# Shematic.net
KiCad netlist of a schematic drawn in Altium Designer
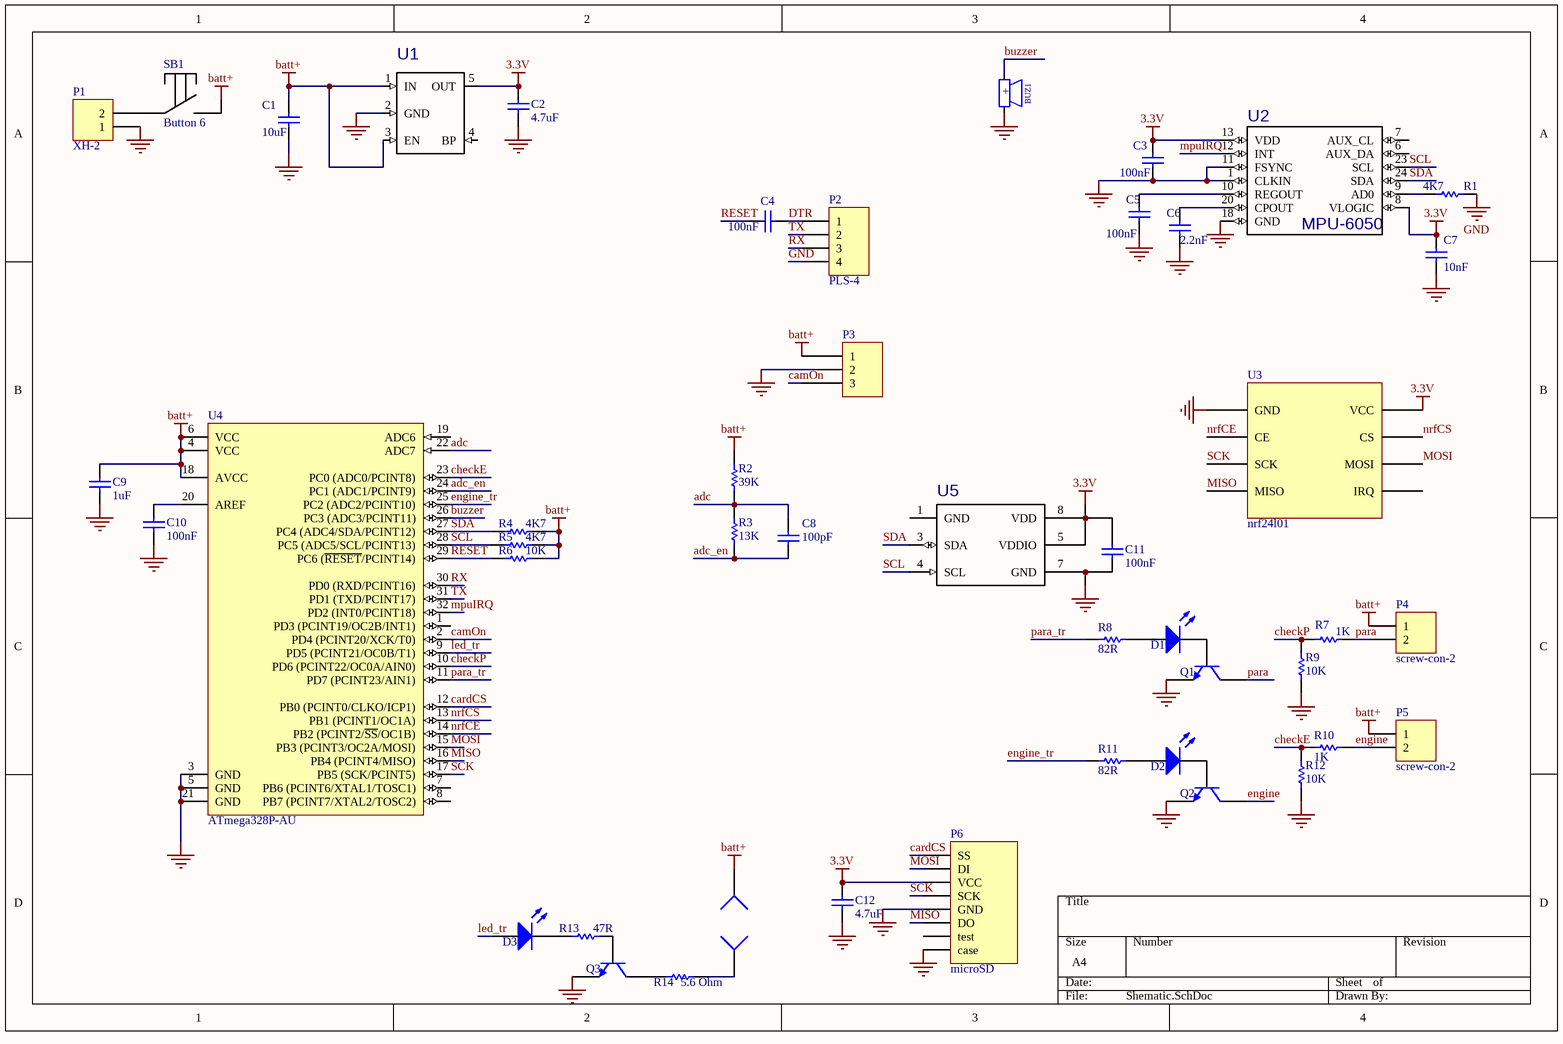
[diagram p0: Shematic.SchDoc]

(export (version "E")
  (design (tool "Eeschema 10.0.6"))
  (components
    (comp (ref "BUZ1")
      (value "Buzzer")
      (footprint "BUZ12X7,6MM")
      (description "BUZ12X7,6MM")
      (libsource (lib "Library") (part "Buzzer"))
    )
    (comp (ref "C1")
      (value "10uF")
      (footprint "CAPC1206(3216)190_N")
      (description "CAP 10uF 50V ±20% 1206 (3216 Metric) Thickness 1.9mm SMD")
      (fields (field (name "TOLERANCE") "Â±20%"))
      (libsource (lib "Altium Content Vault") (part "CMP-1037-04983-1"))
    )
    (comp (ref "C2")
      (value "4.7uF")
      (footprint "CAPC0603(1608)100_N")
      (description "CAP 4.7uF 16V ±20% 0603 (1608 Metric) Thickness 1mm SMD")
      (fields (field (name "TOLERANCE") "Â±20%"))
      (libsource (lib "Altium Content Vault") (part "CMP-1035-02789-1"))
    )
    (comp (ref "C3")
      (value "100nF")
      (footprint "CAPC0603(1608)100_N")
      (description "CAP 100nF 16V ±20% 0603 (1608 Metric) Thickness 1mm SMD")
      (fields (field (name "TOLERANCE") "Â±20%"))
      (libsource (lib "Altium Content Vault") (part "CMP-1035-02585-1"))
    )
    (comp (ref "C4")
      (value "100nF")
      (footprint "CAPC0603(1608)100_N")
      (description "CAP 100nF 16V ±20% 0603 (1608 Metric) Thickness 1mm SMD")
      (fields (field (name "TOLERANCE") "Â±20%"))
      (libsource (lib "Altium Content Vault") (part "CMP-1035-02585-1"))
    )
    (comp (ref "C5")
      (value "100nF")
      (footprint "CAPC0603(1608)100_N")
      (description "CAP 100nF 16V ±20% 0603 (1608 Metric) Thickness 1mm SMD")
      (fields (field (name "TOLERANCE") "Â±20%"))
      (libsource (lib "Altium Content Vault") (part "CMP-1035-02585-1"))
    )
    (comp (ref "C6")
      (value "2.2nF")
      (footprint "CAPC0603(1608)100_L")
      (description "CAP 2.2nF 16V ±20% 0603 (1608 Metric) Thickness 1mm SMD")
      (fields (field (name "TOLERANCE") "Â±20%"))
      (libsource (lib "Altium Content Vault") (part "CMP-1035-02030-1"))
    )
    (comp (ref "C7")
      (value "10nF")
      (footprint "CAPC0603(1608)100_L")
      (description "CAP 10nF 16V ±20% 0603 (1608 Metric) Thickness 1mm SMD")
      (fields (field (name "TOLERANCE") "Â±20%"))
      (libsource (lib "Altium Content Vault") (part "CMP-1035-02312-1"))
    )
    (comp (ref "C8")
      (value "100pF")
      (footprint "CAPC0805(2012)100_L")
      (description "CAP 200pF 16V ±10% 0805 (2012 Metric) Thickness 1mm SMD")
      (fields (field (name "TOLERANCE") "Â±10%"))
      (libsource (lib "Altium Content Vault") (part "CMP-1036-02260-1"))
    )
    (comp (ref "C9")
      (value "1uF")
      (footprint "CAPC0603(1608)100_L")
      (description "CAP 1uF 16V ±20% 0603 (1608 Metric) Thickness 1mm SMD")
      (fields (field (name "TOLERANCE") "Â±20%"))
      (libsource (lib "Altium Content Vault") (part "CMP-1035-02738-1"))
    )
    (comp (ref "C10")
      (value "100nF")
      (footprint "CAPC0603(1608)100_N")
      (description "CAP 100nF 16V ±20% 0603 (1608 Metric) Thickness 1mm SMD")
      (fields (field (name "TOLERANCE") "Â±20%"))
      (libsource (lib "Altium Content Vault") (part "CMP-1035-02585-1"))
    )
    (comp (ref "C11")
      (value "100nF")
      (footprint "CAPC0603(1608)100_N")
      (description "CAP 100nF 16V ±20% 0603 (1608 Metric) Thickness 1mm SMD")
      (fields (field (name "TOLERANCE") "Â±20%"))
      (libsource (lib "Altium Content Vault") (part "CMP-1035-02585-1"))
    )
    (comp (ref "C12")
      (value "4.7uF")
      (footprint "CAPC0603(1608)100_N")
      (description "CAP 4.7uF 16V ±20% 0603 (1608 Metric) Thickness 1mm SMD")
      (fields (field (name "TOLERANCE") "Â±20%"))
      (libsource (lib "Altium Content Vault") (part "CMP-1035-02789-1"))
    )
    (comp (ref "D1")
      (value "~")
      (footprint "LED0805")
      (description "Typical INFRARED GaAs LED")
      (fields (field (name "PUBLISHER") "Altium Limited"))
      (libsource (lib "Library") (part "LED0"))
    )
    (comp (ref "D2")
      (value "~")
      (footprint "LED0805")
      (description "Typical INFRARED GaAs LED")
      (fields (field (name "PUBLISHER") "Altium Limited"))
      (libsource (lib "Library") (part "LED0"))
    )
    (comp (ref "D3")
      (value "~")
      (footprint "LED0805")
      (description "Typical INFRARED GaAs LED")
      (fields (field (name "PUBLISHER") "Altium Limited"))
      (libsource (lib "Library") (part "LED0"))
    )
    (comp (ref "J1")
      (value "~")
      (footprint "PIN1")
      (description "Socket")
      (fields (field (name "PUBLISHER") "Altium Limited"))
      (libsource (lib "Miscellaneous Connectors") (part "Socket"))
    )
    (comp (ref "J2")
      (value "~")
      (footprint "PIN1")
      (description "Socket")
      (fields (field (name "PUBLISHER") "Altium Limited"))
      (libsource (lib "Miscellaneous Connectors") (part "Socket"))
    )
    (comp (ref "P1")
      (value "XH-2")
      (footprint "Library_pcb:XH-2")
      (description "XH 2-pin, 2.4mm pitch")
      (fields (field (name "PUBLISHER") "Altium Limited"))
      (libsource (lib "Library") (part "XH-2"))
    )
    (comp (ref "P2")
      (value "PLS-4")
      (footprint "Connectors:PLS-4")
      (description "Single row pins")
      (libsource (lib "Connectors") (part "PLS-4"))
    )
    (comp (ref "P3")
      (value "XH2.54-3")
      (footprint "Connectors:XH2.54-3")
      (libsource (lib "Connectors") (part "XH2.54-3"))
    )
    (comp (ref "P4")
      (value "screw-con-2")
      (footprint "Library_pcb:screw-con-2")
      (description "screw con 2-pin, 5.08mm pitch")
      (fields (field (name "PUBLISHER") "Altium Limited"))
      (libsource (lib "Library") (part "screw-con-2"))
    )
    (comp (ref "P5")
      (value "screw-con-2")
      (footprint "Library_pcb:screw-con-2")
      (description "screw con 2-pin, 5.08mm pitch")
      (fields (field (name "PUBLISHER") "Altium Limited"))
      (libsource (lib "Library") (part "screw-con-2"))
    )
    (comp (ref "P6")
      (value "microSD")
      (footprint "Library_pcb:microSD holder")
      (description "microSD holder")
      (fields (field (name "PUBLISHER") "Altium Limited"))
      (libsource (lib "Library") (part "microSD"))
    )
    (comp (ref "Q1")
      (value "MMBT2222A")
      (footprint "INF-SOT23_L")
      (description "NPN Silicon Switching Transistor, 40 V VCEO, 600 mA IC, SOT23, Reel, Green")
      (fields (field (name "MANUFACTURER") "Infineon"))
      (libsource (lib "Altium Content Vault") (part "CMP-1178-00009-1"))
    )
    (comp (ref "Q2")
      (value "MMBT2222A")
      (footprint "INF-SOT23_N")
      (description "NPN Silicon Switching Transistor, 40 V VCEO, 600 mA IC, SOT23, Reel, Green")
      (fields (field (name "MANUFACTURER") "Infineon"))
      (libsource (lib "Altium Content Vault") (part "CMP-1178-00009-1"))
    )
    (comp (ref "Q3")
      (value "MMBT2222A")
      (footprint "INF-SOT23_M")
      (description "NPN Silicon Switching Transistor, 40 V VCEO, 600 mA IC, SOT23, Reel, Green")
      (fields (field (name "MANUFACTURER") "Infineon"))
      (libsource (lib "Altium Content Vault") (part "CMP-1178-00009-1"))
    )
    (comp (ref "R1")
      (value "4K7")
      (footprint "RESC0603(1608)_N")
      (description "4K7 0.1W 5% 0603 (1608 Metric)  SMD")
      (fields (field (name "TOLERANCE") "5 %") (field (name "POWER") "0.1 W"))
      (libsource (lib "Altium Content Vault") (part "CMP-1012-00090-1"))
    )
    (comp (ref "R2")
      (value "39K")
      (footprint "Miscellaneous Devices:6-0805_L")
      (description "39K 0.25W 5% 1206 (3216 Metric)  SMD")
      (fields (field (name "TOLERANCE") "5 %") (field (name "POWER") "0.25 W"))
      (libsource (lib "altium-import") (part "root_1_CMP-1014-00112-1_"))
    )
    (comp (ref "R3")
      (value "13K")
      (footprint "RESC0805(2012)_L")
      (description "13K 0.125W 5% 0805 (2012 Metric)  SMD")
      (fields (field (name "POWER") "0.125 W") (field (name "TOLERANCE") "5 %"))
      (libsource (lib "Altium Content Vault") (part "CMP-1013-00101-1"))
    )
    (comp (ref "R4")
      (value "4K7")
      (footprint "RESC0603(1608)_N")
      (description "4K7 0.1W 5% 0603 (1608 Metric)  SMD")
      (fields (field (name "TOLERANCE") "5 %") (field (name "POWER") "0.1 W"))
      (libsource (lib "Altium Content Vault") (part "CMP-1012-00090-1"))
    )
    (comp (ref "R5")
      (value "4K7")
      (footprint "RESC0603(1608)_N")
      (description "4K7 0.1W 5% 0603 (1608 Metric)  SMD")
      (fields (field (name "TOLERANCE") "5 %") (field (name "POWER") "0.1 W"))
      (libsource (lib "Altium Content Vault") (part "CMP-1012-00090-1"))
    )
    (comp (ref "R6")
      (value "10K")
      (footprint "Miscellaneous Devices:6-0805_L")
      (fields (field (name "POWER") "0.25 W") (field (name "TOLERANCE") "5 %"))
      (libsource (lib "altium-import") (part "root_0_CMP-1014-00098-1_"))
    )
    (comp (ref "R7")
      (value "1K")
      (footprint "RESC0805(2012)_N")
      (description "1K 0.125W 5% 0805 (2012 Metric)  SMD")
      (fields (field (name "POWER") "0.125 W") (field (name "TOLERANCE") "5 %"))
      (libsource (lib "Altium Content Vault") (part "CMP-1013-00074-1"))
    )
    (comp (ref "R8")
      (value "82R")
      (footprint "RESC0805(2012)_L")
      (description "2R4 0.125W 5% 0805 (2012 Metric)  SMD")
      (fields (field (name "POWER") "0.125 W") (field (name "TOLERANCE") "5 %"))
      (libsource (lib "Altium Content Vault") (part "CMP-1013-00011-1"))
    )
    (comp (ref "R9")
      (value "10K")
      (footprint "RESC0805(2012)_L")
      (description "10K 0.125W 5% 0805 (2012 Metric)  SMD")
      (fields (field (name "POWER") "0.125 W") (field (name "TOLERANCE") "5 %"))
      (libsource (lib "Altium Content Vault") (part "CMP-1013-00098-1"))
    )
    (comp (ref "R10")
      (value "1K")
      (footprint "RESC1206(3216)_N")
      (description "1K 0.25W 5% 1206 (3216 Metric)  SMD")
      (fields (field (name "TOLERANCE") "5 %") (field (name "POWER") "0.25 W"))
      (libsource (lib "Altium Content Vault") (part "CMP-1014-00074-1"))
    )
    (comp (ref "R11")
      (value "82R")
      (footprint "RESC0805(2012)_L")
      (description "2R4 0.125W 5% 0805 (2012 Metric)  SMD")
      (fields (field (name "POWER") "0.125 W") (field (name "TOLERANCE") "5 %"))
      (libsource (lib "Altium Content Vault") (part "CMP-1013-00011-1"))
    )
    (comp (ref "R12")
      (value "10K")
      (footprint "RESC0805(2012)_L")
      (description "10K 0.125W 5% 0805 (2012 Metric)  SMD")
      (fields (field (name "POWER") "0.125 W") (field (name "TOLERANCE") "5 %"))
      (libsource (lib "Altium Content Vault") (part "CMP-1013-00098-1"))
    )
    (comp (ref "R13")
      (value "47R")
      (footprint "RESC0805(2012)_N")
      (description "270R 0.125W 5% 0805 (2012 Metric)  SMD")
      (fields (field (name "POWER") "0.125 W") (field (name "TOLERANCE") "5 %"))
      (libsource (lib "Altium Content Vault") (part "CMP-1013-00060-1"))
    )
    (comp (ref "R14")
      (value "5.6 Ohm")
      (footprint "RESC0805(2012)_M")
      (description "100R 0.125W 5% 0805 (2012 Metric)  SMD")
      (fields (field (name "TOLERANCE") "5 %") (field (name "POWER") "0.125 W"))
      (libsource (lib "Altium Content Vault") (part "CMP-1013-00050-1"))
    )
    (comp (ref "SB1")
      (value "Button 6")
      (footprint "Library_pcb:Button - 6 mm")
      (libsource (lib "Library") (part "Button 6"))
    )
    (comp (ref "U1")
      (value "MIC5205")
      (footprint "SOT23-5L_M")
      (description "LDO (KB33)")
      (libsource (lib "Library") (part "MIC5205"))
    )
    (comp (ref "U2")
      (value "MPU-6050")
      (footprint "QFN-24-4MM2")
      (libsource (lib "Library") (part "MPU-6050"))
    )
    (comp (ref "U3")
      (value "nrf24l01")
      (footprint "NRF24l01 ant")
      (description "Wirless module 2.4GHz")
      (libsource (lib "Library") (part "NRF24L01"))
    )
    (comp (ref "U4")
      (value "ATmega328P-AU")
      (footprint "32A_M")
      (libsource (lib "Altium Content Vault") (part "MC-8B-ATM48-SQ32"))
    )
    (comp (ref "U5")
      (value "BMP280")
      (footprint "Library_pcb:BMP280")
      (libsource (lib "Library") (part "BMP280"))
    )
  )
  (nets
    (net (code "1") (name "/DTR") (class "Default")
      (node (ref "C4") (pin "2") (pinfunction "2_2") (pintype "passive"))
      (node (ref "P2") (pin "1") (pinfunction "1_1") (pintype "passive"))
    )
    (net (code "2") (name "/MISO") (class "Default")
      (node (ref "P6") (pin "7") (pinfunction "DO_7") (pintype "passive"))
      (node (ref "U3") (pin "7") (pinfunction "MISO_7") (pintype "passive"))
      (node (ref "U4") (pin "16") (pinfunction "PB4_(PCINT4/MISO)_16") (pintype "bidirectional"))
    )
    (net (code "3") (name "/MOSI") (class "Default")
      (node (ref "P6") (pin "3") (pinfunction "DI_3") (pintype "passive"))
      (node (ref "U3") (pin "6") (pinfunction "MOSI_6") (pintype "passive"))
      (node (ref "U4") (pin "15") (pinfunction "PB3_(PCINT3/OC2A/MOSI)_15") (pintype "bidirectional"))
    )
    (net (code "4") (name "/RESET") (class "Default")
      (node (ref "C4") (pin "1") (pinfunction "1_1") (pintype "passive"))
      (node (ref "R6") (pin "1") (pinfunction "1_1") (pintype "passive"))
      (node (ref "U4") (pin "29") (pinfunction "PC6_(~{RESET}/PCINT14)_29") (pintype "bidirectional"))
    )
    (net (code "5") (name "/RX") (class "Default")
      (node (ref "P2") (pin "3") (pinfunction "3_3") (pintype "passive"))
      (node (ref "U4") (pin "30") (pinfunction "PD0_(RXD/PCINT16)_30") (pintype "bidirectional"))
    )
    (net (code "6") (name "/SCK") (class "Default")
      (node (ref "P6") (pin "5") (pinfunction "SCK_5") (pintype "passive"))
      (node (ref "U3") (pin "5") (pinfunction "SCK_5") (pintype "passive"))
      (node (ref "U4") (pin "17") (pinfunction "PB5_(SCK/PCINT5)_17") (pintype "bidirectional"))
    )
    (net (code "7") (name "/SCL") (class "Default")
      (node (ref "R5") (pin "1") (pinfunction "1_1") (pintype "passive"))
      (node (ref "U2") (pin "23") (pinfunction "SCL_23") (pintype "bidirectional"))
      (node (ref "U4") (pin "28") (pinfunction "PC5_(ADC5/SCL/PCINT13)_28") (pintype "bidirectional"))
      (node (ref "U5") (pin "4") (pinfunction "SCL_4") (pintype "input"))
    )
    (net (code "8") (name "/SDA") (class "Default")
      (node (ref "R4") (pin "1") (pinfunction "1_1") (pintype "passive"))
      (node (ref "U2") (pin "24") (pinfunction "SDA_24") (pintype "bidirectional"))
      (node (ref "U4") (pin "27") (pinfunction "PC4_(ADC4/SDA/PCINT12)_27") (pintype "bidirectional"))
      (node (ref "U5") (pin "3") (pinfunction "SDA_3") (pintype "bidirectional"))
    )
    (net (code "9") (name "/TX") (class "Default")
      (node (ref "P2") (pin "2") (pinfunction "2_2") (pintype "passive"))
      (node (ref "U4") (pin "31") (pinfunction "PD1_(TXD/PCINT17)_31") (pintype "bidirectional"))
    )
    (net (code "10") (name "/adc") (class "Default")
      (node (ref "C8") (pin "2") (pinfunction "2_2") (pintype "passive"))
      (node (ref "R2") (pin "1") (pinfunction "1_1") (pintype "passive"))
      (node (ref "R3") (pin "1") (pinfunction "1_1") (pintype "passive"))
      (node (ref "U4") (pin "22") (pinfunction "ADC7_22") (pintype "input"))
    )
    (net (code "11") (name "/adc_en") (class "Default")
      (node (ref "C8") (pin "1") (pinfunction "1_1") (pintype "passive"))
      (node (ref "R3") (pin "2") (pinfunction "2_2") (pintype "passive"))
      (node (ref "U4") (pin "24") (pinfunction "PC1_(ADC1/PCINT9)_24") (pintype "bidirectional"))
    )
    (net (code "12") (name "/buzzer") (class "Default")
      (node (ref "BUZ1") (pin "2") (pinfunction "2_2") (pintype "passive"))
      (node (ref "U4") (pin "26") (pinfunction "PC3_(ADC3/PCINT11)_26") (pintype "bidirectional"))
    )
    (net (code "13") (name "/camOn") (class "Default")
      (node (ref "P3") (pin "3") (pinfunction "3_3") (pintype "passive"))
      (node (ref "U4") (pin "2") (pinfunction "PD4_(PCINT20/XCK/T0)_2") (pintype "bidirectional"))
    )
    (net (code "14") (name "/cardCS") (class "Default")
      (node (ref "P6") (pin "2") (pinfunction "SS_2") (pintype "passive"))
      (node (ref "U4") (pin "12") (pinfunction "PB0_(PCINT0/CLKO/ICP1)_12") (pintype "bidirectional"))
    )
    (net (code "15") (name "/checkE") (class "Default")
      (node (ref "R10") (pin "1") (pinfunction "1_1") (pintype "passive"))
      (node (ref "R12") (pin "2") (pinfunction "2_2") (pintype "passive"))
      (node (ref "U4") (pin "23") (pinfunction "PC0_(ADC0/PCINT8)_23") (pintype "bidirectional"))
    )
    (net (code "16") (name "/checkP") (class "Default")
      (node (ref "R7") (pin "1") (pinfunction "1_1") (pintype "passive"))
      (node (ref "R9") (pin "2") (pinfunction "2_2") (pintype "passive"))
      (node (ref "U4") (pin "10") (pinfunction "PD6_(PCINT22/OC0A/AIN0)_10") (pintype "bidirectional"))
    )
    (net (code "17") (name "/engine") (class "Default")
      (node (ref "P5") (pin "2") (pinfunction "2_2") (pintype "passive"))
      (node (ref "Q2") (pin "3") (pinfunction "C_3") (pintype "passive"))
      (node (ref "R10") (pin "2") (pinfunction "2_2") (pintype "passive"))
    )
    (net (code "18") (name "/engine_tr") (class "Default")
      (node (ref "R11") (pin "1") (pinfunction "1_1") (pintype "passive"))
      (node (ref "U4") (pin "25") (pinfunction "PC2_(ADC2/PCINT10)_25") (pintype "bidirectional"))
    )
    (net (code "19") (name "/led_tr") (class "Default")
      (node (ref "D3") (pin "1") (pinfunction "A_1") (pintype "passive"))
      (node (ref "U4") (pin "9") (pinfunction "PD5_(PCINT21/OC0B/T1)_9") (pintype "bidirectional"))
    )
    (net (code "20") (name "/mpuIRQ") (class "Default")
      (node (ref "U2") (pin "12") (pinfunction "INT_12") (pintype "bidirectional"))
      (node (ref "U4") (pin "32") (pinfunction "PD2_(INT0/PCINT18)_32") (pintype "bidirectional"))
    )
    (net (code "21") (name "/nrfCE") (class "Default")
      (node (ref "U3") (pin "3") (pinfunction "CE_3") (pintype "passive"))
      (node (ref "U4") (pin "14") (pinfunction "PB2_(PCINT2/~{SS}/OC1B)_14") (pintype "bidirectional"))
    )
    (net (code "22") (name "/nrfCS") (class "Default")
      (node (ref "U3") (pin "4") (pinfunction "CS_4") (pintype "passive"))
      (node (ref "U4") (pin "13") (pinfunction "PB1_(PCINT1/OC1A)_13") (pintype "bidirectional"))
    )
    (net (code "23") (name "/para") (class "Default")
      (node (ref "P4") (pin "2") (pinfunction "2_2") (pintype "passive"))
      (node (ref "Q1") (pin "3") (pinfunction "C_3") (pintype "passive"))
      (node (ref "R7") (pin "2") (pinfunction "2_2") (pintype "passive"))
    )
    (net (code "24") (name "/para_tr") (class "Default")
      (node (ref "R8") (pin "1") (pinfunction "1_1") (pintype "passive"))
      (node (ref "U4") (pin "11") (pinfunction "PD7_(PCINT23/AIN1)_11") (pintype "bidirectional"))
    )
    (net (code "25") (name "3.3V") (class "Default")
      (node (ref "C11") (pin "2") (pinfunction "2_2") (pintype "passive"))
      (node (ref "C12") (pin "2") (pinfunction "2_2") (pintype "passive"))
      (node (ref "C2") (pin "2") (pinfunction "2_2") (pintype "passive"))
      (node (ref "C3") (pin "1") (pinfunction "1_1") (pintype "passive"))
      (node (ref "C7") (pin "2") (pinfunction "2_2") (pintype "passive"))
      (node (ref "P6") (pin "4") (pinfunction "VCC_4") (pintype "passive"))
      (node (ref "U1") (pin "5") (pinfunction "OUT_5") (pintype "passive"))
      (node (ref "U2") (pin "13") (pinfunction "VDD_13") (pintype "bidirectional"))
      (node (ref "U2") (pin "8") (pinfunction "VLOGIC_8") (pintype "bidirectional"))
      (node (ref "U3") (pin "2") (pinfunction "VCC_2") (pintype "passive"))
      (node (ref "U5") (pin "5") (pinfunction "VDDIO_5") (pintype "power_in"))
      (node (ref "U5") (pin "8") (pinfunction "VDD_8") (pintype "power_in"))
    )
    (net (code "26") (name "GND") (class "Default")
      (node (ref "BUZ1") (pin "1") (pinfunction "1_1") (pintype "passive"))
      (node (ref "C1") (pin "1") (pinfunction "1_1") (pintype "passive"))
      (node (ref "C10") (pin "1") (pinfunction "1_1") (pintype "passive"))
      (node (ref "C11") (pin "1") (pinfunction "1_1") (pintype "passive"))
      (node (ref "C12") (pin "1") (pinfunction "1_1") (pintype "passive"))
      (node (ref "C2") (pin "1") (pinfunction "1_1") (pintype "passive"))
      (node (ref "C3") (pin "2") (pinfunction "2_2") (pintype "passive"))
      (node (ref "C5") (pin "1") (pinfunction "1_1") (pintype "passive"))
      (node (ref "C6") (pin "1") (pinfunction "1_1") (pintype "passive"))
      (node (ref "C7") (pin "1") (pinfunction "1_1") (pintype "passive"))
      (node (ref "C9") (pin "1") (pinfunction "1_1") (pintype "passive"))
      (node (ref "P1") (pin "1") (pinfunction "1_1") (pintype "passive"))
      (node (ref "P2") (pin "4") (pinfunction "4_4") (pintype "passive"))
      (node (ref "P3") (pin "2") (pinfunction "2_2") (pintype "passive"))
      (node (ref "P6") (pin "0") (pinfunction "case_0") (pintype "passive"))
      (node (ref "P6") (pin "6") (pinfunction "GND_6") (pintype "passive"))
      (node (ref "Q1") (pin "2") (pinfunction "E_2") (pintype "passive"))
      (node (ref "Q2") (pin "2") (pinfunction "E_2") (pintype "passive"))
      (node (ref "Q3") (pin "2") (pinfunction "E_2") (pintype "passive"))
      (node (ref "R1") (pin "2") (pinfunction "2_2") (pintype "passive"))
      (node (ref "R12") (pin "1") (pinfunction "1_1") (pintype "passive"))
      (node (ref "R9") (pin "1") (pinfunction "1_1") (pintype "passive"))
      (node (ref "U1") (pin "2") (pinfunction "GND_2") (pintype "input"))
      (node (ref "U2") (pin "1") (pinfunction "CLKIN_1") (pintype "bidirectional"))
      (node (ref "U2") (pin "11") (pinfunction "FSYNC_11") (pintype "bidirectional"))
      (node (ref "U2") (pin "18") (pinfunction "GND_18") (pintype "bidirectional"))
      (node (ref "U3") (pin "1") (pinfunction "GND_1") (pintype "passive"))
      (node (ref "U4") (pin "21") (pinfunction "GND_21") (pintype "power_in"))
      (node (ref "U4") (pin "3") (pinfunction "GND_3") (pintype "power_in"))
      (node (ref "U4") (pin "5") (pinfunction "GND_5") (pintype "power_in"))
      (node (ref "U5") (pin "7") (pinfunction "GND_7") (pintype "power_in"))
    )
    (net (code "27") (name "Net-(D1-A)") (class "Default")
      (node (ref "D1") (pin "1") (pinfunction "A_1") (pintype "passive"))
      (node (ref "R8") (pin "2") (pinfunction "2_2") (pintype "passive"))
    )
    (net (code "28") (name "Net-(D1-K)") (class "Default")
      (node (ref "D1") (pin "2") (pinfunction "K_2") (pintype "passive"))
      (node (ref "Q1") (pin "1") (pinfunction "B_1") (pintype "passive"))
    )
    (net (code "29") (name "Net-(D2-A)") (class "Default")
      (node (ref "D2") (pin "1") (pinfunction "A_1") (pintype "passive"))
      (node (ref "R11") (pin "2") (pinfunction "2_2") (pintype "passive"))
    )
    (net (code "30") (name "Net-(D2-K)") (class "Default")
      (node (ref "D2") (pin "2") (pinfunction "K_2") (pintype "passive"))
      (node (ref "Q2") (pin "1") (pinfunction "B_1") (pintype "passive"))
    )
    (net (code "31") (name "Net-(D3-K)") (class "Default")
      (node (ref "D3") (pin "2") (pinfunction "K_2") (pintype "passive"))
      (node (ref "R13") (pin "1") (pinfunction "1_1") (pintype "passive"))
    )
    (net (code "32") (name "Net-(J2-Pad1)") (class "Default")
      (node (ref "J2") (pin "1") (pinfunction "1_1") (pintype "passive"))
      (node (ref "R14") (pin "2") (pinfunction "2_2") (pintype "passive"))
    )
    (net (code "33") (name "Net-(P1-Pad2)") (class "Default")
      (node (ref "P1") (pin "2") (pinfunction "2_2") (pintype "passive"))
      (node (ref "SB1") (pin "1") (pinfunction "1_1") (pintype "passive"))
    )
    (net (code "34") (name "Net-(Q3-B)") (class "Default")
      (node (ref "Q3") (pin "1") (pinfunction "B_1") (pintype "passive"))
      (node (ref "R13") (pin "2") (pinfunction "2_2") (pintype "passive"))
    )
    (net (code "35") (name "Net-(Q3-C)") (class "Default")
      (node (ref "Q3") (pin "3") (pinfunction "C_3") (pintype "passive"))
      (node (ref "R14") (pin "1") (pinfunction "1_1") (pintype "passive"))
    )
    (net (code "36") (name "Net-(U2-AD0)") (class "Default")
      (node (ref "R1") (pin "1") (pinfunction "1_1") (pintype "passive"))
      (node (ref "U2") (pin "9") (pinfunction "AD0_9") (pintype "bidirectional"))
    )
    (net (code "37") (name "Net-(U2-CPOUT)") (class "Default")
      (node (ref "C6") (pin "2") (pinfunction "2_2") (pintype "passive"))
      (node (ref "U2") (pin "20") (pinfunction "CPOUT_20") (pintype "bidirectional"))
    )
    (net (code "38") (name "Net-(U2-REGOUT)") (class "Default")
      (node (ref "C5") (pin "2") (pinfunction "2_2") (pintype "passive"))
      (node (ref "U2") (pin "10") (pinfunction "REGOUT_10") (pintype "bidirectional"))
    )
    (net (code "39") (name "Net-(U4-AREF)") (class "Default")
      (node (ref "C10") (pin "2") (pinfunction "2_2") (pintype "passive"))
      (node (ref "U4") (pin "20") (pinfunction "AREF_20") (pintype "passive"))
    )
    (net (code "40") (name "batt+") (class "Default")
      (node (ref "C1") (pin "2") (pinfunction "2_2") (pintype "passive"))
      (node (ref "C9") (pin "2") (pinfunction "2_2") (pintype "passive"))
      (node (ref "J1") (pin "1") (pinfunction "1_1") (pintype "passive"))
      (node (ref "P3") (pin "1") (pinfunction "1_1") (pintype "passive"))
      (node (ref "P4") (pin "1") (pinfunction "1_1") (pintype "passive"))
      (node (ref "P5") (pin "1") (pinfunction "1_1") (pintype "passive"))
      (node (ref "R2") (pin "2") (pinfunction "2_2") (pintype "passive"))
      (node (ref "R4") (pin "2") (pinfunction "2_2") (pintype "passive"))
      (node (ref "R5") (pin "2") (pinfunction "2_2") (pintype "passive"))
      (node (ref "R6") (pin "2") (pinfunction "2_2") (pintype "passive"))
      (node (ref "SB1") (pin "2") (pinfunction "2_2") (pintype "passive"))
      (node (ref "U1") (pin "1") (pinfunction "IN_1") (pintype "input"))
      (node (ref "U1") (pin "3") (pinfunction "EN_3") (pintype "input"))
      (node (ref "U4") (pin "18") (pinfunction "AVCC_18") (pintype "power_in"))
      (node (ref "U4") (pin "4") (pinfunction "VCC_4") (pintype "power_in"))
      (node (ref "U4") (pin "6") (pinfunction "VCC_6") (pintype "power_in"))
    )
    (net (code "41") (name "unconnected-(P6-test-Pad9)") (class "Default")
      (node (ref "P6") (pin "9") (pinfunction "test_9") (pintype "passive"))
    )
    (net (code "42") (name "unconnected-(SB1-Pad3)") (class "Default")
      (node (ref "SB1") (pin "3") (pinfunction "3_3") (pintype "passive"))
    )
    (net (code "43") (name "unconnected-(SB1-Pad4)") (class "Default")
      (node (ref "SB1") (pin "4") (pinfunction "4_4") (pintype "passive"))
    )
    (net (code "44") (name "unconnected-(SB1-Pad5)") (class "Default")
      (node (ref "SB1") (pin "5") (pinfunction "5_5") (pintype "passive"))
    )
    (net (code "45") (name "unconnected-(SB1-Pad6)") (class "Default")
      (node (ref "SB1") (pin "6") (pinfunction "6_6") (pintype "passive"))
    )
    (net (code "46") (name "unconnected-(U1-BP-Pad4)") (class "Default")
      (node (ref "U1") (pin "4") (pinfunction "BP_4") (pintype "input"))
    )
    (net (code "47") (name "unconnected-(U2-AUX_CL-Pad7)") (class "Default")
      (node (ref "U2") (pin "7") (pinfunction "AUX_CL_7") (pintype "bidirectional"))
    )
    (net (code "48") (name "unconnected-(U2-AUX_DA-Pad6)") (class "Default")
      (node (ref "U2") (pin "6") (pinfunction "AUX_DA_6") (pintype "bidirectional"))
    )
    (net (code "49") (name "unconnected-(U3-IRQ-Pad8)") (class "Default")
      (node (ref "U3") (pin "8") (pinfunction "IRQ_8") (pintype "passive"))
    )
    (net (code "50") (name "unconnected-(U4-ADC6-Pad19)") (class "Default")
      (node (ref "U4") (pin "19") (pinfunction "ADC6_19") (pintype "input"))
    )
    (net (code "51") (name "unconnected-(U4-PB6_(PCINT6{slash}XTAL1{slash}TOSC1)-Pad7)") (class "Default")
      (node (ref "U4") (pin "7") (pinfunction "PB6_(PCINT6/XTAL1/TOSC1)_7") (pintype "bidirectional"))
    )
    (net (code "52") (name "unconnected-(U4-PB7_(PCINT7{slash}XTAL2{slash}TOSC2)-Pad8)") (class "Default")
      (node (ref "U4") (pin "8") (pinfunction "PB7_(PCINT7/XTAL2/TOSC2)_8") (pintype "bidirectional"))
    )
    (net (code "53") (name "unconnected-(U4-PD3_(PCINT19{slash}OC2B{slash}INT1)-Pad1)") (class "Default")
      (node (ref "U4") (pin "1") (pinfunction "PD3_(PCINT19/OC2B/INT1)_1") (pintype "bidirectional"))
    )
    (net (code "54") (name "unconnected-(U5-GND-Pad1)") (class "Default")
      (node (ref "U5") (pin "1") (pinfunction "GND_1") (pintype "power_in"))
    )
  )
)
